# dsky_md_3_0v.net
KiCad netlist of a schematic drawn in EAGLE
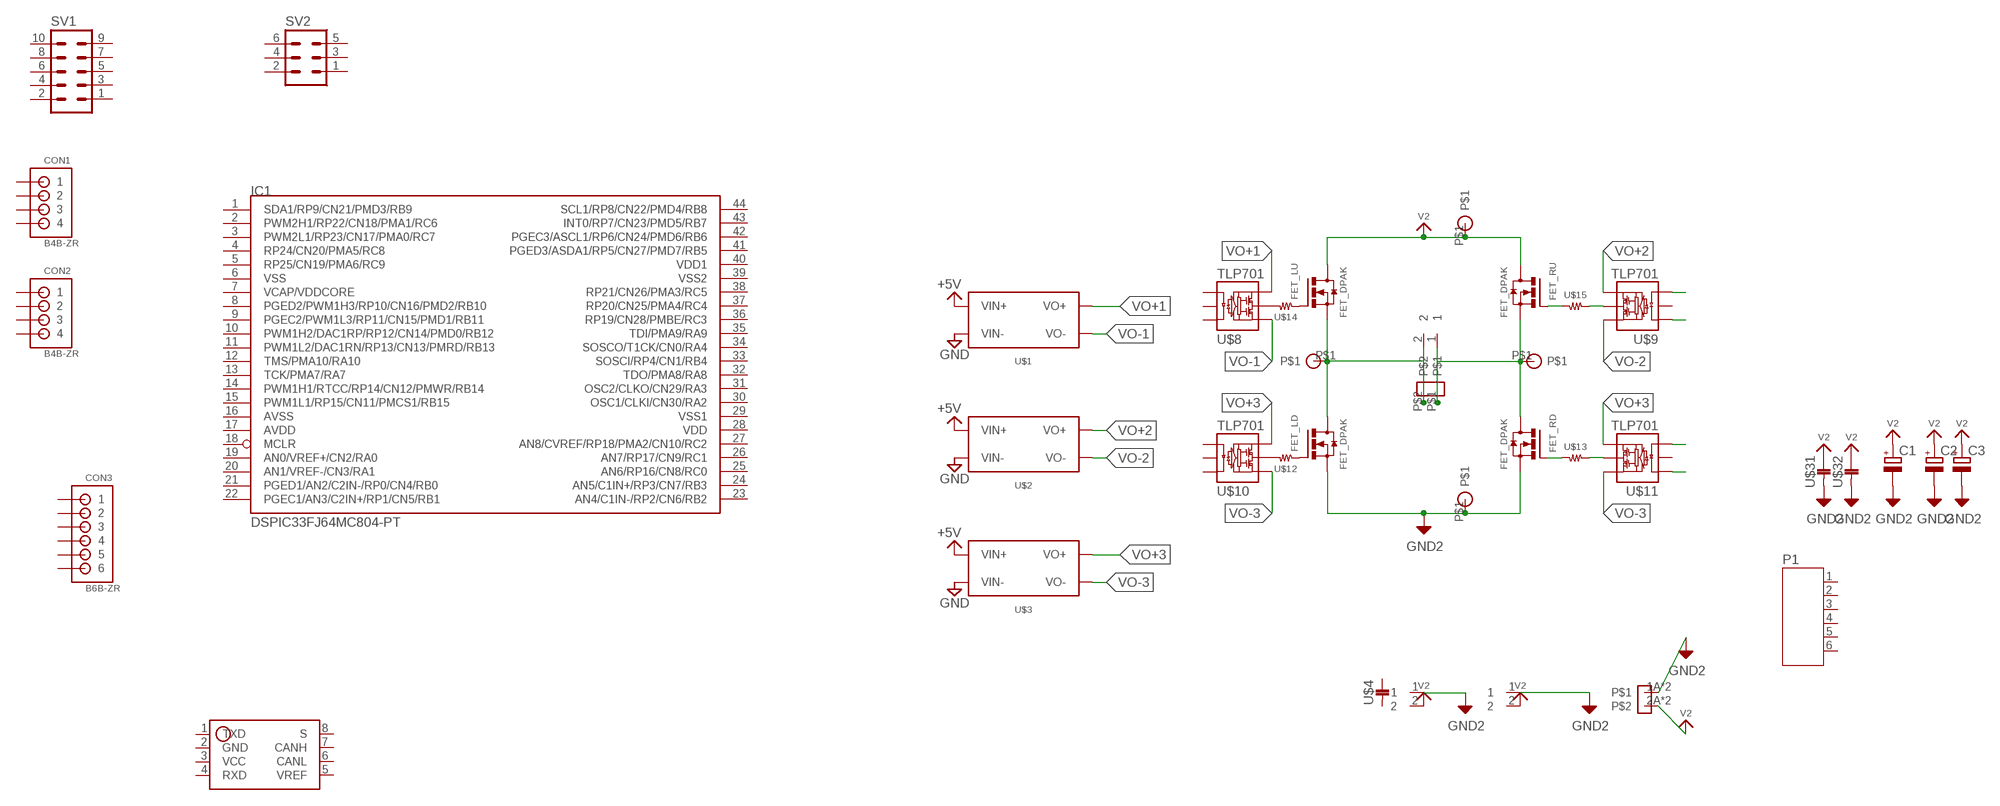
[diagram p0: schematic, sheet 1]

(export (version "E")
  (design (tool "Eeschema 10.0.6"))
  (components
    (comp (ref "C1")
      (value "CPOL-EUE3.5-8")
      (footprint "eagle-import:E3,5-8")
      (libsource (lib "eagle-import") (part "CPOL-EUE3.5-8"))
    )
    (comp (ref "C2")
      (value "CPOL-EUE3.5-8")
      (footprint "eagle-import:E3,5-8")
      (libsource (lib "eagle-import") (part "CPOL-EUE3.5-8"))
    )
    (comp (ref "C3")
      (value "CPOL-EU150CLZ-1010")
      (footprint "eagle-import:150CLZ-1010")
      (libsource (lib "eagle-import") (part "CPOL-EU150CLZ-1010"))
    )
    (comp (ref "CON1")
      (value "B4B-ZR")
      (footprint "eagle-import:B4B-ZR")
      (libsource (lib "eagle-import") (part "B4B-ZR"))
    )
    (comp (ref "CON2")
      (value "B4B-ZR")
      (footprint "eagle-import:B4B-ZR")
      (libsource (lib "eagle-import") (part "B4B-ZR"))
    )
    (comp (ref "CON3")
      (value "B6B-ZR")
      (footprint "eagle-import:B6B-ZR")
      (libsource (lib "eagle-import") (part "B6B-ZR"))
    )
    (comp (ref "FET_LD")
      (value "FET_DPAK")
      (footprint "eagle-import:DPAK")
      (libsource (lib "eagle-import") (part "FET_DPAK"))
    )
    (comp (ref "FET_LU")
      (value "FET_DPAK")
      (footprint "eagle-import:DPAK")
      (libsource (lib "eagle-import") (part "FET_DPAK"))
    )
    (comp (ref "FET_RD")
      (value "FET_DPAK")
      (footprint "eagle-import:DPAK")
      (libsource (lib "eagle-import") (part "FET_DPAK"))
    )
    (comp (ref "FET_RU")
      (value "FET_DPAK")
      (footprint "eagle-import:DPAK")
      (libsource (lib "eagle-import") (part "FET_DPAK"))
    )
    (comp (ref "IC1")
      (value "DSPIC33FJ64MC804-PT")
      (footprint "eagle-import:TQFP44")
      (libsource (lib "eagle-import") (part "DSPIC33FJ64MC804-PT"))
    )
    (comp (ref "P1")
      (value "JST-PH6")
      (footprint "eagle-import:JST-PH6")
      (libsource (lib "eagle-import") (part "JST-PH6"))
    )
    (comp (ref "SV1")
      (value "ML10")
      (footprint "eagle-import:ML10")
      (libsource (lib "eagle-import") (part "ML10"))
    )
    (comp (ref "SV2")
      (value "ML6")
      (footprint "eagle-import:ML6")
      (libsource (lib "eagle-import") (part "ML6"))
    )
    (comp (ref "U$1")
      (value "MAU100")
      (footprint "eagle-import:MAU")
      (libsource (lib "eagle-import") (part "MAU100"))
    )
    (comp (ref "U$2")
      (value "MAU100")
      (footprint "eagle-import:MAU")
      (libsource (lib "eagle-import") (part "MAU100"))
    )
    (comp (ref "U$3")
      (value "MAU100")
      (footprint "eagle-import:MAU")
      (libsource (lib "eagle-import") (part "MAU100"))
    )
    (comp (ref "U$4")
      (value "1608")
      (footprint "eagle-import:1608")
      (libsource (lib "eagle-import") (part "1608"))
    )
    (comp (ref "U$5")
      (value "VL_2")
      (footprint "eagle-import:VL_2")
      (libsource (lib "eagle-import") (part "VL_2"))
    )
    (comp (ref "U$8")
      (value "TLP701")
      (footprint "eagle-import:11-5J1")
      (libsource (lib "eagle-import") (part "TLP701"))
    )
    (comp (ref "U$9")
      (value "TLP701")
      (footprint "eagle-import:11-5J1")
      (libsource (lib "eagle-import") (part "TLP701"))
    )
    (comp (ref "U$10")
      (value "TLP701")
      (footprint "eagle-import:11-5J1")
      (libsource (lib "eagle-import") (part "TLP701"))
    )
    (comp (ref "U$11")
      (value "TLP701")
      (footprint "eagle-import:11-5J1")
      (libsource (lib "eagle-import") (part "TLP701"))
    )
    (comp (ref "U$12")
      (value "RESISTOR__SMD")
      (footprint "eagle-import:1608")
      (libsource (lib "eagle-import") (part "RESISTOR__SMD"))
    )
    (comp (ref "U$13")
      (value "RESISTOR__SMD")
      (footprint "eagle-import:1608")
      (libsource (lib "eagle-import") (part "RESISTOR__SMD"))
    )
    (comp (ref "U$14")
      (value "RESISTOR__SMD")
      (footprint "eagle-import:1608")
      (libsource (lib "eagle-import") (part "RESISTOR__SMD"))
    )
    (comp (ref "U$15")
      (value "RESISTOR__SMD")
      (footprint "eagle-import:1608")
      (libsource (lib "eagle-import") (part "RESISTOR__SMD"))
    )
    (comp (ref "U$16")
      (value "VL_2")
      (footprint "eagle-import:VL_2")
      (libsource (lib "eagle-import") (part "VL_2"))
    )
    (comp (ref "U$21")
      (value "HAN_FAST")
      (footprint "eagle-import:HOLE_4.4MM")
      (libsource (lib "eagle-import") (part "HAN_FAST"))
    )
    (comp (ref "U$22")
      (value "HAN_FAST")
      (footprint "eagle-import:HOLE_4.4MM")
      (libsource (lib "eagle-import") (part "HAN_FAST"))
    )
    (comp (ref "U$23")
      (value "VL_2")
      (footprint "eagle-import:VL_2")
      (libsource (lib "eagle-import") (part "VL_2"))
    )
    (comp (ref "U$24")
      (value "TERMINAL_2P")
      (footprint "eagle-import:TERMINAL_2P")
      (libsource (lib "eagle-import") (part "TERMINAL_2P"))
    )
    (comp (ref "U$31")
      (value "3225")
      (footprint "eagle-import:3225")
      (libsource (lib "eagle-import") (part "3225"))
    )
    (comp (ref "U$32")
      (value "3225")
      (footprint "eagle-import:3225")
      (libsource (lib "eagle-import") (part "3225"))
    )
    (comp (ref "U$43")
      (value "HAN_FAST")
      (footprint "eagle-import:HOLE_4.4MM")
      (libsource (lib "eagle-import") (part "HAN_FAST"))
    )
    (comp (ref "U$44")
      (value "HAN_FAST")
      (footprint "eagle-import:HOLE_4.4MM")
      (libsource (lib "eagle-import") (part "HAN_FAST"))
    )
    (comp (ref "U$45")
      (value "SN65HVD1050")
      (footprint "eagle-import:SOIC8")
      (libsource (lib "eagle-import") (part "SN65HVD1050"))
    )
    (comp (ref "U$46")
      (value "ML_300_2P")
      (footprint "eagle-import:ML_300_2P")
      (libsource (lib "eagle-import") (part "ML_300_2P"))
    )
  )
  (nets
    (net (code "1") (name "+5V") (class "Default")
      (node (ref "U$1") (pin "P$1") (pinfunction "VIN+_P$1") (pintype "bidirectional"))
      (node (ref "U$2") (pin "P$1") (pinfunction "VIN+_P$1") (pintype "bidirectional"))
      (node (ref "U$3") (pin "P$1") (pinfunction "VIN+_P$1") (pintype "bidirectional"))
    )
    (net (code "2") (name "/AVDD") (class "Default")
      (node (ref "IC1") (pin "17") (pinfunction "AVDD_17") (pintype "power_in"))
    )
    (net (code "3") (name "/AVSS") (class "Default")
      (node (ref "IC1") (pin "16") (pinfunction "AVSS_16") (pintype "power_in"))
    )
    (net (code "4") (name "/VCAP{slash}VDDCORE") (class "Default")
      (node (ref "IC1") (pin "7") (pinfunction "VCAP/VDDCORE_7") (pintype "power_in"))
    )
    (net (code "5") (name "/VDD") (class "Default")
      (node (ref "IC1") (pin "28") (pinfunction "VDD_28") (pintype "power_in"))
    )
    (net (code "6") (name "/VDD1") (class "Default")
      (node (ref "IC1") (pin "40") (pinfunction "VDD1_40") (pintype "power_in"))
    )
    (net (code "7") (name "/VSS") (class "Default")
      (node (ref "IC1") (pin "6") (pinfunction "VSS_6") (pintype "power_in"))
    )
    (net (code "8") (name "/VSS1") (class "Default")
      (node (ref "IC1") (pin "29") (pinfunction "VSS1_29") (pintype "power_in"))
    )
    (net (code "9") (name "/VSS2") (class "Default")
      (node (ref "IC1") (pin "39") (pinfunction "VSS2_39") (pintype "power_in"))
    )
    (net (code "10") (name "GND") (class "Default")
      (node (ref "U$1") (pin "P$2") (pinfunction "VIN-_P$2") (pintype "bidirectional"))
      (node (ref "U$2") (pin "P$2") (pinfunction "VIN-_P$2") (pintype "bidirectional"))
      (node (ref "U$3") (pin "P$2") (pinfunction "VIN-_P$2") (pintype "bidirectional"))
    )
    (net (code "11") (name "GND2") (class "Default")
      (node (ref "C1") (pin "-") (pinfunction "-_-") (pintype "passive"))
      (node (ref "C2") (pin "-") (pinfunction "-_-") (pintype "passive"))
      (node (ref "C3") (pin "-") (pinfunction "-_-") (pintype "passive"))
      (node (ref "FET_LD") (pin "3") (pinfunction "S_3") (pintype "passive"))
      (node (ref "FET_RD") (pin "3") (pinfunction "S_3") (pintype "passive"))
      (node (ref "U$16") (pin "1") (pinfunction "1_1") (pintype "bidirectional"))
      (node (ref "U$31") (pin "P$2") (pinfunction "2_P$2") (pintype "passive"))
      (node (ref "U$32") (pin "P$2") (pinfunction "2_P$2") (pintype "passive"))
      (node (ref "U$43") (pin "P$1") (pinfunction "P$1_P$1") (pintype "bidirectional"))
      (node (ref "U$46") (pin "1A") (pinfunction "P$1_1A") (pintype "bidirectional"))
      (node (ref "U$46") (pin "1B") (pinfunction "P$1_1B") (pintype "bidirectional"))
      (node (ref "U$5") (pin "1") (pinfunction "1_1") (pintype "bidirectional"))
    )
    (net (code "12") (name "Net-(FET_LD-D)") (class "Default")
      (node (ref "FET_LD") (pin "2") (pinfunction "D_2") (pintype "passive"))
      (node (ref "FET_LU") (pin "3") (pinfunction "S_3") (pintype "passive"))
      (node (ref "U$21") (pin "P$1") (pinfunction "P$1_P$1") (pintype "bidirectional"))
      (node (ref "U$23") (pin "2") (pinfunction "2_2") (pintype "bidirectional"))
      (node (ref "U$24") (pin "P$2") (pinfunction "P$2_P$2") (pintype "bidirectional"))
    )
    (net (code "13") (name "Net-(FET_LD-G)") (class "Default")
      (node (ref "FET_LD") (pin "1") (pinfunction "G_1") (pintype "passive"))
      (node (ref "U$12") (pin "1") (pinfunction "P$1_1") (pintype "passive"))
    )
    (net (code "14") (name "Net-(FET_LU-G)") (class "Default")
      (node (ref "FET_LU") (pin "1") (pinfunction "G_1") (pintype "passive"))
      (node (ref "U$14") (pin "1") (pinfunction "P$1_1") (pintype "passive"))
    )
    (net (code "15") (name "Net-(FET_RD-D)") (class "Default")
      (node (ref "FET_RD") (pin "2") (pinfunction "D_2") (pintype "passive"))
      (node (ref "FET_RU") (pin "3") (pinfunction "S_3") (pintype "passive"))
      (node (ref "U$22") (pin "P$1") (pinfunction "P$1_P$1") (pintype "bidirectional"))
      (node (ref "U$23") (pin "1") (pinfunction "1_1") (pintype "bidirectional"))
      (node (ref "U$24") (pin "P$1") (pinfunction "P$1_P$1") (pintype "bidirectional"))
    )
    (net (code "16") (name "Net-(FET_RD-G)") (class "Default")
      (node (ref "FET_RD") (pin "1") (pinfunction "G_1") (pintype "passive"))
      (node (ref "U$13") (pin "1") (pinfunction "P$1_1") (pintype "passive"))
    )
    (net (code "17") (name "Net-(FET_RU-G)") (class "Default")
      (node (ref "FET_RU") (pin "1") (pinfunction "G_1") (pintype "passive"))
      (node (ref "U$15") (pin "1") (pinfunction "P$1_1") (pintype "passive"))
    )
    (net (code "18") (name "Net-(U$10-OUT)") (class "Default")
      (node (ref "U$10") (pin "5") (pinfunction "OUT_5") (pintype "output"))
      (node (ref "U$12") (pin "2") (pinfunction "P$2_2") (pintype "passive"))
    )
    (net (code "19") (name "Net-(U$11-OUT)") (class "Default")
      (node (ref "U$11") (pin "5") (pinfunction "OUT_5") (pintype "output"))
      (node (ref "U$13") (pin "2") (pinfunction "P$2_2") (pintype "passive"))
    )
    (net (code "20") (name "Net-(U$14-P$2)") (class "Default")
      (node (ref "U$14") (pin "2") (pinfunction "P$2_2") (pintype "passive"))
      (node (ref "U$8") (pin "5") (pinfunction "OUT_5") (pintype "output"))
    )
    (net (code "21") (name "Net-(U$15-P$2)") (class "Default")
      (node (ref "U$15") (pin "2") (pinfunction "P$2_2") (pintype "passive"))
      (node (ref "U$9") (pin "5") (pinfunction "OUT_5") (pintype "output"))
    )
    (net (code "22") (name "V2") (class "Default")
      (node (ref "C1") (pin "+") (pinfunction "+_+") (pintype "passive"))
      (node (ref "C2") (pin "+") (pinfunction "+_+") (pintype "passive"))
      (node (ref "C3") (pin "+") (pinfunction "+_+") (pintype "passive"))
      (node (ref "FET_LU") (pin "2") (pinfunction "D_2") (pintype "passive"))
      (node (ref "FET_RU") (pin "2") (pinfunction "D_2") (pintype "passive"))
      (node (ref "U$16") (pin "2") (pinfunction "2_2") (pintype "bidirectional"))
      (node (ref "U$31") (pin "P$1") (pinfunction "1_P$1") (pintype "passive"))
      (node (ref "U$32") (pin "P$1") (pinfunction "1_P$1") (pintype "passive"))
      (node (ref "U$44") (pin "P$1") (pinfunction "P$1_P$1") (pintype "bidirectional"))
      (node (ref "U$46") (pin "2A") (pinfunction "P$2_2A") (pintype "bidirectional"))
      (node (ref "U$46") (pin "2B") (pinfunction "P$2_2B") (pintype "bidirectional"))
      (node (ref "U$5") (pin "2") (pinfunction "2_2") (pintype "bidirectional"))
    )
    (net (code "23") (name "VO+1") (class "Default")
      (node (ref "U$1") (pin "P$5") (pinfunction "VO+_P$5") (pintype "bidirectional"))
      (node (ref "U$8") (pin "6") (pinfunction "VCC_6") (pintype "bidirectional"))
    )
    (net (code "24") (name "VO+2") (class "Default")
      (node (ref "U$2") (pin "P$5") (pinfunction "VO+_P$5") (pintype "bidirectional"))
      (node (ref "U$9") (pin "6") (pinfunction "VCC_6") (pintype "bidirectional"))
    )
    (net (code "25") (name "VO+3") (class "Default")
      (node (ref "U$10") (pin "6") (pinfunction "VCC_6") (pintype "bidirectional"))
      (node (ref "U$11") (pin "6") (pinfunction "VCC_6") (pintype "bidirectional"))
      (node (ref "U$3") (pin "P$5") (pinfunction "VO+_P$5") (pintype "bidirectional"))
    )
    (net (code "26") (name "VO-1") (class "Default")
      (node (ref "U$1") (pin "P$3") (pinfunction "VO-_P$3") (pintype "bidirectional"))
      (node (ref "U$8") (pin "4") (pinfunction "GND_4") (pintype "bidirectional"))
    )
    (net (code "27") (name "VO-2") (class "Default")
      (node (ref "U$2") (pin "P$3") (pinfunction "VO-_P$3") (pintype "bidirectional"))
      (node (ref "U$9") (pin "4") (pinfunction "GND_4") (pintype "bidirectional"))
    )
    (net (code "28") (name "VO-3") (class "Default")
      (node (ref "U$10") (pin "4") (pinfunction "GND_4") (pintype "bidirectional"))
      (node (ref "U$11") (pin "4") (pinfunction "GND_4") (pintype "bidirectional"))
      (node (ref "U$3") (pin "P$3") (pinfunction "VO-_P$3") (pintype "bidirectional"))
    )
    (net (code "29") (name "unconnected-(CON1-Pad1)") (class "Default")
      (node (ref "CON1") (pin "1") (pinfunction "1_1") (pintype "bidirectional"))
    )
    (net (code "30") (name "unconnected-(CON1-Pad2)") (class "Default")
      (node (ref "CON1") (pin "2") (pinfunction "2_2") (pintype "bidirectional"))
    )
    (net (code "31") (name "unconnected-(CON1-Pad3)") (class "Default")
      (node (ref "CON1") (pin "3") (pinfunction "3_3") (pintype "bidirectional"))
    )
    (net (code "32") (name "unconnected-(CON1-Pad4)") (class "Default")
      (node (ref "CON1") (pin "4") (pinfunction "4_4") (pintype "bidirectional"))
    )
    (net (code "33") (name "unconnected-(CON2-Pad1)") (class "Default")
      (node (ref "CON2") (pin "1") (pinfunction "1_1") (pintype "bidirectional"))
    )
    (net (code "34") (name "unconnected-(CON2-Pad2)") (class "Default")
      (node (ref "CON2") (pin "2") (pinfunction "2_2") (pintype "bidirectional"))
    )
    (net (code "35") (name "unconnected-(CON2-Pad3)") (class "Default")
      (node (ref "CON2") (pin "3") (pinfunction "3_3") (pintype "bidirectional"))
    )
    (net (code "36") (name "unconnected-(CON2-Pad4)") (class "Default")
      (node (ref "CON2") (pin "4") (pinfunction "4_4") (pintype "bidirectional"))
    )
    (net (code "37") (name "unconnected-(CON3-Pad1)") (class "Default")
      (node (ref "CON3") (pin "1") (pinfunction "1_1") (pintype "bidirectional"))
    )
    (net (code "38") (name "unconnected-(CON3-Pad2)") (class "Default")
      (node (ref "CON3") (pin "2") (pinfunction "2_2") (pintype "bidirectional"))
    )
    (net (code "39") (name "unconnected-(CON3-Pad3)") (class "Default")
      (node (ref "CON3") (pin "3") (pinfunction "3_3") (pintype "bidirectional"))
    )
    (net (code "40") (name "unconnected-(CON3-Pad4)") (class "Default")
      (node (ref "CON3") (pin "4") (pinfunction "4_4") (pintype "bidirectional"))
    )
    (net (code "41") (name "unconnected-(CON3-Pad5)") (class "Default")
      (node (ref "CON3") (pin "5") (pinfunction "5_5") (pintype "bidirectional"))
    )
    (net (code "42") (name "unconnected-(CON3-Pad6)") (class "Default")
      (node (ref "CON3") (pin "6") (pinfunction "6_6") (pintype "bidirectional"))
    )
    (net (code "43") (name "unconnected-(IC1-AN0{slash}VREF+{slash}CN2{slash}RA0-Pad19)") (class "Default")
      (node (ref "IC1") (pin "19") (pinfunction "AN0/VREF+/CN2/RA0_19") (pintype "bidirectional"))
    )
    (net (code "44") (name "unconnected-(IC1-AN1{slash}VREF-{slash}CN3{slash}RA1-Pad20)") (class "Default")
      (node (ref "IC1") (pin "20") (pinfunction "AN1/VREF-/CN3/RA1_20") (pintype "bidirectional"))
    )
    (net (code "45") (name "unconnected-(IC1-AN4{slash}C1IN-{slash}RP2{slash}CN6{slash}RB2-Pad23)") (class "Default")
      (node (ref "IC1") (pin "23") (pinfunction "AN4/C1IN-/RP2/CN6/RB2_23") (pintype "bidirectional"))
    )
    (net (code "46") (name "unconnected-(IC1-AN5{slash}C1IN+{slash}RP3{slash}CN7{slash}RB3-Pad24)") (class "Default")
      (node (ref "IC1") (pin "24") (pinfunction "AN5/C1IN+/RP3/CN7/RB3_24") (pintype "bidirectional"))
    )
    (net (code "47") (name "unconnected-(IC1-AN6{slash}RP16{slash}CN8{slash}RC0-Pad25)") (class "Default")
      (node (ref "IC1") (pin "25") (pinfunction "AN6/RP16/CN8/RC0_25") (pintype "bidirectional"))
    )
    (net (code "48") (name "unconnected-(IC1-AN7{slash}RP17{slash}CN9{slash}RC1-Pad26)") (class "Default")
      (node (ref "IC1") (pin "26") (pinfunction "AN7/RP17/CN9/RC1_26") (pintype "bidirectional"))
    )
    (net (code "49") (name "unconnected-(IC1-AN8{slash}CVREF{slash}RP18{slash}PMA2{slash}CN10{slash}RC2-Pad27)") (class "Default")
      (node (ref "IC1") (pin "27") (pinfunction "AN8/CVREF/RP18/PMA2/CN10/RC2_27") (pintype "bidirectional"))
    )
    (net (code "50") (name "unconnected-(IC1-INT0{slash}RP7{slash}CN23{slash}PMD5{slash}RB7-Pad43)") (class "Default")
      (node (ref "IC1") (pin "43") (pinfunction "INT0/RP7/CN23/PMD5/RB7_43") (pintype "bidirectional"))
    )
    (net (code "51") (name "unconnected-(IC1-MCLR-Pad18)") (class "Default")
      (node (ref "IC1") (pin "18") (pinfunction "MCLR_18") (pintype "input"))
    )
    (net (code "52") (name "unconnected-(IC1-OSC1{slash}CLKI{slash}CN30{slash}RA2-Pad30)") (class "Default")
      (node (ref "IC1") (pin "30") (pinfunction "OSC1/CLKI/CN30/RA2_30") (pintype "bidirectional"))
    )
    (net (code "53") (name "unconnected-(IC1-OSC2{slash}CLKO{slash}CN29{slash}RA3-Pad31)") (class "Default")
      (node (ref "IC1") (pin "31") (pinfunction "OSC2/CLKO/CN29/RA3_31") (pintype "bidirectional"))
    )
    (net (code "54") (name "unconnected-(IC1-PGEC1{slash}AN3{slash}C2IN+{slash}RP1{slash}CN5{slash}RB1-Pad22)") (class "Default")
      (node (ref "IC1") (pin "22") (pinfunction "PGEC1/AN3/C2IN+/RP1/CN5/RB1_22") (pintype "bidirectional"))
    )
    (net (code "55") (name "unconnected-(IC1-PGEC2{slash}PWM1L3{slash}RP11{slash}CN15{slash}PMD1{slash}RB11-Pad9)") (class "Default")
      (node (ref "IC1") (pin "9") (pinfunction "PGEC2/PWM1L3/RP11/CN15/PMD1/RB11_9") (pintype "bidirectional"))
    )
    (net (code "56") (name "unconnected-(IC1-PGEC3{slash}ASCL1{slash}RP6{slash}CN24{slash}PMD6{slash}RB6-Pad42)") (class "Default")
      (node (ref "IC1") (pin "42") (pinfunction "PGEC3/ASCL1/RP6/CN24/PMD6/RB6_42") (pintype "bidirectional"))
    )
    (net (code "57") (name "unconnected-(IC1-PGED1{slash}AN2{slash}C2IN-{slash}RP0{slash}CN4{slash}RB0-Pad21)") (class "Default")
      (node (ref "IC1") (pin "21") (pinfunction "PGED1/AN2/C2IN-/RP0/CN4/RB0_21") (pintype "bidirectional"))
    )
    (net (code "58") (name "unconnected-(IC1-PGED2{slash}PWM1H3{slash}RP10{slash}CN16{slash}PMD2{slash}RB10-Pad8)") (class "Default")
      (node (ref "IC1") (pin "8") (pinfunction "PGED2/PWM1H3/RP10/CN16/PMD2/RB10_8") (pintype "bidirectional"))
    )
    (net (code "59") (name "unconnected-(IC1-PGED3{slash}ASDA1{slash}RP5{slash}CN27{slash}PMD7{slash}RB5-Pad41)") (class "Default")
      (node (ref "IC1") (pin "41") (pinfunction "PGED3/ASDA1/RP5/CN27/PMD7/RB5_41") (pintype "bidirectional"))
    )
    (net (code "60") (name "unconnected-(IC1-PWM1H1{slash}RTCC{slash}RP14{slash}CN12{slash}PMWR{slash}RB14-Pad14)") (class "Default")
      (node (ref "IC1") (pin "14") (pinfunction "PWM1H1/RTCC/RP14/CN12/PMWR/RB14_14") (pintype "bidirectional"))
    )
    (net (code "61") (name "unconnected-(IC1-PWM1H2{slash}DAC1RP{slash}RP12{slash}CN14{slash}PMD0{slash}RB12-Pad10)") (class "Default")
      (node (ref "IC1") (pin "10") (pinfunction "PWM1H2/DAC1RP/RP12/CN14/PMD0/RB12_10") (pintype "bidirectional"))
    )
    (net (code "62") (name "unconnected-(IC1-PWM1L1{slash}RP15{slash}CN11{slash}PMCS1{slash}RB15-Pad15)") (class "Default")
      (node (ref "IC1") (pin "15") (pinfunction "PWM1L1/RP15/CN11/PMCS1/RB15_15") (pintype "bidirectional"))
    )
    (net (code "63") (name "unconnected-(IC1-PWM1L2{slash}DAC1RN{slash}RP13{slash}CN13{slash}PMRD{slash}RB13-Pad11)") (class "Default")
      (node (ref "IC1") (pin "11") (pinfunction "PWM1L2/DAC1RN/RP13/CN13/PMRD/RB13_11") (pintype "bidirectional"))
    )
    (net (code "64") (name "unconnected-(IC1-PWM2H1{slash}RP22{slash}CN18{slash}PMA1{slash}RC6-Pad2)") (class "Default")
      (node (ref "IC1") (pin "2") (pinfunction "PWM2H1/RP22/CN18/PMA1/RC6_2") (pintype "bidirectional"))
    )
    (net (code "65") (name "unconnected-(IC1-PWM2L1{slash}RP23{slash}CN17{slash}PMA0{slash}RC7-Pad3)") (class "Default")
      (node (ref "IC1") (pin "3") (pinfunction "PWM2L1/RP23/CN17/PMA0/RC7_3") (pintype "bidirectional"))
    )
    (net (code "66") (name "unconnected-(IC1-RP19{slash}CN28{slash}PMBE{slash}RC3-Pad36)") (class "Default")
      (node (ref "IC1") (pin "36") (pinfunction "RP19/CN28/PMBE/RC3_36") (pintype "bidirectional"))
    )
    (net (code "67") (name "unconnected-(IC1-RP20{slash}CN25{slash}PMA4{slash}RC4-Pad37)") (class "Default")
      (node (ref "IC1") (pin "37") (pinfunction "RP20/CN25/PMA4/RC4_37") (pintype "bidirectional"))
    )
    (net (code "68") (name "unconnected-(IC1-RP21{slash}CN26{slash}PMA3{slash}RC5-Pad38)") (class "Default")
      (node (ref "IC1") (pin "38") (pinfunction "RP21/CN26/PMA3/RC5_38") (pintype "bidirectional"))
    )
    (net (code "69") (name "unconnected-(IC1-RP24{slash}CN20{slash}PMA5{slash}RC8-Pad4)") (class "Default")
      (node (ref "IC1") (pin "4") (pinfunction "RP24/CN20/PMA5/RC8_4") (pintype "bidirectional"))
    )
    (net (code "70") (name "unconnected-(IC1-RP25{slash}CN19{slash}PMA6{slash}RC9-Pad5)") (class "Default")
      (node (ref "IC1") (pin "5") (pinfunction "RP25/CN19/PMA6/RC9_5") (pintype "bidirectional"))
    )
    (net (code "71") (name "unconnected-(IC1-SCL1{slash}RP8{slash}CN22{slash}PMD4{slash}RB8-Pad44)") (class "Default")
      (node (ref "IC1") (pin "44") (pinfunction "SCL1/RP8/CN22/PMD4/RB8_44") (pintype "bidirectional"))
    )
    (net (code "72") (name "unconnected-(IC1-SDA1{slash}RP9{slash}CN21{slash}PMD3{slash}RB9-Pad1)") (class "Default")
      (node (ref "IC1") (pin "1") (pinfunction "SDA1/RP9/CN21/PMD3/RB9_1") (pintype "bidirectional"))
    )
    (net (code "73") (name "unconnected-(IC1-SOSCI{slash}RP4{slash}CN1{slash}RB4-Pad33)") (class "Default")
      (node (ref "IC1") (pin "33") (pinfunction "SOSCI/RP4/CN1/RB4_33") (pintype "bidirectional"))
    )
    (net (code "74") (name "unconnected-(IC1-SOSCO{slash}T1CK{slash}CN0{slash}RA4-Pad34)") (class "Default")
      (node (ref "IC1") (pin "34") (pinfunction "SOSCO/T1CK/CN0/RA4_34") (pintype "bidirectional"))
    )
    (net (code "75") (name "unconnected-(IC1-TCK{slash}PMA7{slash}RA7-Pad13)") (class "Default")
      (node (ref "IC1") (pin "13") (pinfunction "TCK/PMA7/RA7_13") (pintype "bidirectional"))
    )
    (net (code "76") (name "unconnected-(IC1-TDI{slash}PMA9{slash}RA9-Pad35)") (class "Default")
      (node (ref "IC1") (pin "35") (pinfunction "TDI/PMA9/RA9_35") (pintype "bidirectional"))
    )
    (net (code "77") (name "unconnected-(IC1-TDO{slash}PMA8{slash}RA8-Pad32)") (class "Default")
      (node (ref "IC1") (pin "32") (pinfunction "TDO/PMA8/RA8_32") (pintype "bidirectional"))
    )
    (net (code "78") (name "unconnected-(IC1-TMS{slash}PMA10{slash}RA10-Pad12)") (class "Default")
      (node (ref "IC1") (pin "12") (pinfunction "TMS/PMA10/RA10_12") (pintype "bidirectional"))
    )
    (net (code "79") (name "unconnected-(P1-Pad1)") (class "Default")
      (node (ref "P1") (pin "1") (pinfunction "1_1") (pintype "passive"))
    )
    (net (code "80") (name "unconnected-(P1-Pad2)") (class "Default")
      (node (ref "P1") (pin "2") (pinfunction "2_2") (pintype "passive"))
    )
    (net (code "81") (name "unconnected-(P1-Pad3)") (class "Default")
      (node (ref "P1") (pin "3") (pinfunction "3_3") (pintype "passive"))
    )
    (net (code "82") (name "unconnected-(P1-Pad4)") (class "Default")
      (node (ref "P1") (pin "4") (pinfunction "4_4") (pintype "passive"))
    )
    (net (code "83") (name "unconnected-(P1-Pad5)") (class "Default")
      (node (ref "P1") (pin "5") (pinfunction "5_5") (pintype "passive"))
    )
    (net (code "84") (name "unconnected-(P1-Pad6)") (class "Default")
      (node (ref "P1") (pin "6") (pinfunction "6_6") (pintype "passive"))
    )
    (net (code "85") (name "unconnected-(SV1-Pad1)") (class "Default")
      (node (ref "SV1") (pin "1") (pinfunction "1_1") (pintype "passive"))
    )
    (net (code "86") (name "unconnected-(SV1-Pad2)") (class "Default")
      (node (ref "SV1") (pin "2") (pinfunction "2_2") (pintype "passive"))
    )
    (net (code "87") (name "unconnected-(SV1-Pad3)") (class "Default")
      (node (ref "SV1") (pin "3") (pinfunction "3_3") (pintype "passive"))
    )
    (net (code "88") (name "unconnected-(SV1-Pad4)") (class "Default")
      (node (ref "SV1") (pin "4") (pinfunction "4_4") (pintype "passive"))
    )
    (net (code "89") (name "unconnected-(SV1-Pad5)") (class "Default")
      (node (ref "SV1") (pin "5") (pinfunction "5_5") (pintype "passive"))
    )
    (net (code "90") (name "unconnected-(SV1-Pad6)") (class "Default")
      (node (ref "SV1") (pin "6") (pinfunction "6_6") (pintype "passive"))
    )
    (net (code "91") (name "unconnected-(SV1-Pad7)") (class "Default")
      (node (ref "SV1") (pin "7") (pinfunction "7_7") (pintype "passive"))
    )
    (net (code "92") (name "unconnected-(SV1-Pad8)") (class "Default")
      (node (ref "SV1") (pin "8") (pinfunction "8_8") (pintype "passive"))
    )
    (net (code "93") (name "unconnected-(SV1-Pad9)") (class "Default")
      (node (ref "SV1") (pin "9") (pinfunction "9_9") (pintype "passive"))
    )
    (net (code "94") (name "unconnected-(SV1-Pad10)") (class "Default")
      (node (ref "SV1") (pin "10") (pinfunction "10_10") (pintype "passive"))
    )
    (net (code "95") (name "unconnected-(SV2-Pad1)") (class "Default")
      (node (ref "SV2") (pin "1") (pinfunction "1_1") (pintype "passive"))
    )
    (net (code "96") (name "unconnected-(SV2-Pad2)") (class "Default")
      (node (ref "SV2") (pin "2") (pinfunction "2_2") (pintype "passive"))
    )
    (net (code "97") (name "unconnected-(SV2-Pad3)") (class "Default")
      (node (ref "SV2") (pin "3") (pinfunction "3_3") (pintype "passive"))
    )
    (net (code "98") (name "unconnected-(SV2-Pad4)") (class "Default")
      (node (ref "SV2") (pin "4") (pinfunction "4_4") (pintype "passive"))
    )
    (net (code "99") (name "unconnected-(SV2-Pad5)") (class "Default")
      (node (ref "SV2") (pin "5") (pinfunction "5_5") (pintype "passive"))
    )
    (net (code "100") (name "unconnected-(SV2-Pad6)") (class "Default")
      (node (ref "SV2") (pin "6") (pinfunction "6_6") (pintype "passive"))
    )
    (net (code "101") (name "unconnected-(U$4-1-PadP$1)") (class "Default")
      (node (ref "U$4") (pin "P$1") (pinfunction "1_P$1") (pintype "passive"))
    )
    (net (code "102") (name "unconnected-(U$4-2-PadP$2)") (class "Default")
      (node (ref "U$4") (pin "P$2") (pinfunction "2_P$2") (pintype "passive"))
    )
    (net (code "103") (name "unconnected-(U$8-LED+-Pad1)") (class "Default")
      (node (ref "U$8") (pin "1") (pinfunction "LED+_1") (pintype "bidirectional"))
    )
    (net (code "104") (name "unconnected-(U$8-LED--Pad3)") (class "Default")
      (node (ref "U$8") (pin "3") (pinfunction "LED-_3") (pintype "bidirectional"))
    )
    (net (code "105") (name "unconnected-(U$8-NC1-Pad2)") (class "Default")
      (node (ref "U$8") (pin "2") (pinfunction "NC1_2") (pintype "no_connect"))
    )
    (net (code "106") (name "unconnected-(U$9-LED+-Pad1)") (class "Default")
      (node (ref "U$9") (pin "1") (pinfunction "LED+_1") (pintype "bidirectional"))
    )
    (net (code "107") (name "unconnected-(U$9-LED--Pad3)") (class "Default")
      (node (ref "U$9") (pin "3") (pinfunction "LED-_3") (pintype "bidirectional"))
    )
    (net (code "108") (name "unconnected-(U$9-NC1-Pad2)") (class "Default")
      (node (ref "U$9") (pin "2") (pinfunction "NC1_2") (pintype "no_connect"))
    )
    (net (code "109") (name "unconnected-(U$10-LED+-Pad1)") (class "Default")
      (node (ref "U$10") (pin "1") (pinfunction "LED+_1") (pintype "bidirectional"))
    )
    (net (code "110") (name "unconnected-(U$10-LED--Pad3)") (class "Default")
      (node (ref "U$10") (pin "3") (pinfunction "LED-_3") (pintype "bidirectional"))
    )
    (net (code "111") (name "unconnected-(U$10-NC1-Pad2)") (class "Default")
      (node (ref "U$10") (pin "2") (pinfunction "NC1_2") (pintype "no_connect"))
    )
    (net (code "112") (name "unconnected-(U$11-LED+-Pad1)") (class "Default")
      (node (ref "U$11") (pin "1") (pinfunction "LED+_1") (pintype "bidirectional"))
    )
    (net (code "113") (name "unconnected-(U$11-LED--Pad3)") (class "Default")
      (node (ref "U$11") (pin "3") (pinfunction "LED-_3") (pintype "bidirectional"))
    )
    (net (code "114") (name "unconnected-(U$11-NC1-Pad2)") (class "Default")
      (node (ref "U$11") (pin "2") (pinfunction "NC1_2") (pintype "no_connect"))
    )
    (net (code "115") (name "unconnected-(U$45-CANH-Pad7)") (class "Default")
      (node (ref "U$45") (pin "7") (pinfunction "CANH_7") (pintype "bidirectional"))
    )
    (net (code "116") (name "unconnected-(U$45-CANL-Pad6)") (class "Default")
      (node (ref "U$45") (pin "6") (pinfunction "CANL_6") (pintype "bidirectional"))
    )
    (net (code "117") (name "unconnected-(U$45-GND-Pad2)") (class "Default")
      (node (ref "U$45") (pin "2") (pinfunction "GND_2") (pintype "bidirectional"))
    )
    (net (code "118") (name "unconnected-(U$45-RXD-Pad4)") (class "Default")
      (node (ref "U$45") (pin "4") (pinfunction "RXD_4") (pintype "bidirectional"))
    )
    (net (code "119") (name "unconnected-(U$45-S-Pad8)") (class "Default")
      (node (ref "U$45") (pin "8") (pinfunction "S_8") (pintype "bidirectional"))
    )
    (net (code "120") (name "unconnected-(U$45-TXD-Pad1)") (class "Default")
      (node (ref "U$45") (pin "1") (pinfunction "TXD_1") (pintype "bidirectional"))
    )
    (net (code "121") (name "unconnected-(U$45-VCC-Pad3)") (class "Default")
      (node (ref "U$45") (pin "3") (pinfunction "VCC_3") (pintype "bidirectional"))
    )
    (net (code "122") (name "unconnected-(U$45-VREF-Pad5)") (class "Default")
      (node (ref "U$45") (pin "5") (pinfunction "VREF_5") (pintype "bidirectional"))
    )
  )
)
